# 3_USB_TO_UART.net
KiCad netlist of a schematic drawn in Altium Designer
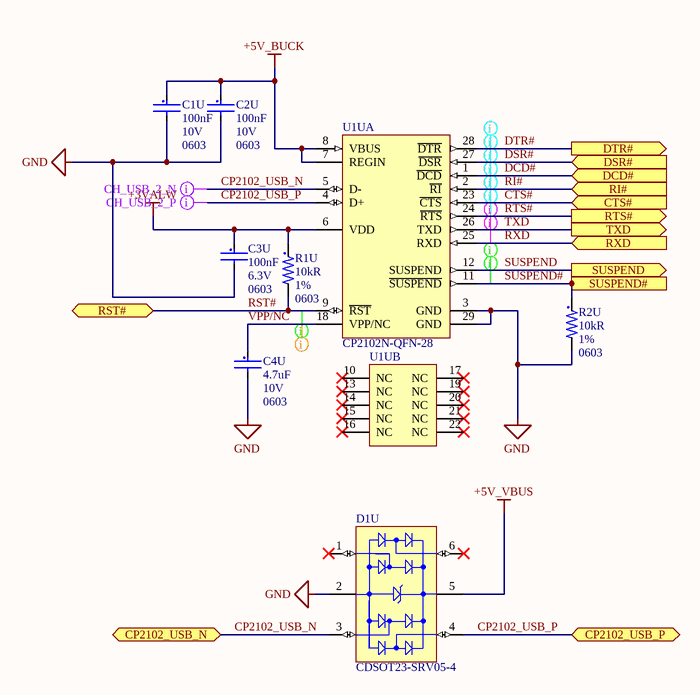
[diagram p0: 3_USB_TO_UART.SchDoc]

(export (version "E")
  (design (tool "Eeschema 10.0.6"))
  (components
    (comp (ref "C1U")
      (value "100nF")
      (footprint "C0603-IPC_C_No_Silk")
      (description "Multilayer Ceramic Capacitor, 0.1 uF, 10 V, ± 10%, X7R, 0603 [1608 Metric]")
      (fields
        (field (name "MANUFACTURER") "KEMET")
        (field (name "MANUFACTURER PART NUMBER") "C0603C104K8RACTU")
        (field (name "VOLTAGE RATING (DC)") "10V")
        (field (name "CASE/PACKAGE") "0603")
      )
      (libsource (lib "Lib_Capacitor_0603") (part "100nF_10V"))
    )
    (comp (ref "C2U")
      (value "100nF")
      (footprint "C0603-IPC_C_No_Silk")
      (description "Multilayer Ceramic Capacitor, 0.1 uF, 10 V, ± 10%, X7R, 0603 [1608 Metric]")
      (fields
        (field (name "MANUFACTURER") "KEMET")
        (field (name "MANUFACTURER PART NUMBER") "C0603C104K8RACTU")
        (field (name "VOLTAGE RATING (DC)") "10V")
        (field (name "CASE/PACKAGE") "0603")
      )
      (libsource (lib "Lib_Capacitor_0603") (part "100nF_10V"))
    )
    (comp (ref "C3U")
      (value "100nF")
      (footprint "C0603-IPC_C_No_Silk")
      (description "Cap Cer 0.1UF 6.3V X7R 0603")
      (fields
        (field (name "MANUFACTURER") "KYOCERA AVX")
        (field (name "MANUFACTURER PART NUMBER") "KGM15AR70J104KM")
        (field (name "VOLTAGE") "6.3V")
        (field (name "PACKAGE") "0603")
      )
      (libsource (lib "Lib_Capacitor_0603") (part "100nF_6.3V"))
    )
    (comp (ref "C4U")
      (value "4.7uF")
      (footprint "C0603-IPC_C_No_Silk")
      (description "Multilayer Ceramic Capacitor, 4.7 uF, 10 V, ± 10%, X5R, 0603 [1608 Metric]")
      (fields
        (field (name "MANUFACTURER") "Samsung")
        (field (name "MANUFACTURER PART NUMBER") "CL10A475KP8NNNC")
        (field (name "VOLTAGE RATING (DC)") "10V")
        (field (name "CASE/PACKAGE") "0603")
      )
      (libsource (lib "Lib_Capacitor_0603") (part "4.7uF_10V"))
    )
    (comp (ref "D1U")
      (value "CDSOT23-SRV05-4")
      (footprint "SOT23-6-IPC_C")
      (description "TVS DIODE 5V 15V SOT23-6")
      (fields
        (field (name "MANUFACTURER") "Bourns Inc.")
        (field (name "OCTOPART") "https://octopart.com/cdsot23-srv05-4-bourns-1679449")
      )
      (libsource (lib "Lib_IC_ESD") (part "SRV05-4"))
    )
    (comp (ref "R1U")
      (value "10kR")
      (footprint "R0603-MFG")
      (description "SMD Chip Resistor, 10 kOhm, ± 1%, 100 mW, 0603 [1608 Metric], Thick Film, General Purpose")
      (fields
        (field (name "MANUFACTURER") "Yageo")
        (field (name "MANUFACTURER PART NUMBER") "RC0603FR-0710KL")
        (field (name "TOLERANCE") "1%")
        (field (name "CASE/PACKAGE") "0603")
      )
      (libsource (lib "Lib_Register_0603") (part "10K"))
    )
    (comp (ref "R2U")
      (value "10kR")
      (footprint "R0603-MFG")
      (description "SMD Chip Resistor, 10 kOhm, ± 1%, 100 mW, 0603 [1608 Metric], Thick Film, General Purpose")
      (fields
        (field (name "MANUFACTURER") "Yageo")
        (field (name "MANUFACTURER PART NUMBER") "RC0603FR-0710KL")
        (field (name "TOLERANCE") "1%")
        (field (name "CASE/PACKAGE") "0603")
      )
      (libsource (lib "Lib_Register_0603") (part "10K"))
    )
    (comp (ref "U1U")
      (value "CP2102N-QFN-28")
      (footprint "QFN28_IPC_A")
      (description "Single-Chip USB to UART Bridge, 1024 Bytes EEPROM, -40 to 85 degC, 28-pin QFN, Tube")
      (fields (field (name "MANUFACTURER") "Silicon Labs") (field (name "PARTNUMBER") "CP2102-GM"))
      (libsource (lib "Lib_IC_UART") (part "CP2102N-QFN-28"))
    )
  )
  (nets
    (net (code "1") (name "+3VALW") (class "Default")
      (node (ref "C3U") (pin "1") (pinfunction "1_1") (pintype "passive"))
      (node (ref "R1U") (pin "1") (pinfunction "1_1") (pintype "passive"))
      (node (ref "U1U") (pin "6") (pinfunction "VDD_6") (pintype "power_in"))
    )
    (net (code "2") (name "+5V_BUCK") (class "Default")
      (node (ref "C1U") (pin "1") (pinfunction "1_1") (pintype "passive"))
      (node (ref "C2U") (pin "1") (pinfunction "1_1") (pintype "passive"))
      (node (ref "U1U") (pin "7") (pinfunction "REGIN_7") (pintype "power_in"))
      (node (ref "U1U") (pin "8") (pinfunction "VBUS_8") (pintype "input"))
    )
    (net (code "3") (name "+5V_VBUS") (class "Default")
      (node (ref "D1U") (pin "5") (pinfunction "VBUS_5") (pintype "power_in"))
    )
    (net (code "4") (name "/CP2102_USB_N") (class "Default")
      (node (ref "D1U") (pin "3") (pinfunction "I/O_2_3") (pintype "bidirectional"))
      (node (ref "U1U") (pin "5") (pinfunction "D-_5") (pintype "bidirectional"))
    )
    (net (code "5") (name "/CP2102_USB_P") (class "Default")
      (node (ref "D1U") (pin "4") (pinfunction "I/O_3_4") (pintype "bidirectional"))
      (node (ref "U1U") (pin "4") (pinfunction "D+_4") (pintype "bidirectional"))
    )
    (net (code "6") (name "/CTS#") (class "Default")
      (node (ref "U1U") (pin "23") (pinfunction "~{CTS}_23") (pintype "input"))
    )
    (net (code "7") (name "/DCD#") (class "Default")
      (node (ref "U1U") (pin "1") (pinfunction "~{DCD}_1") (pintype "input"))
    )
    (net (code "8") (name "/DSR#") (class "Default")
      (node (ref "U1U") (pin "27") (pinfunction "~{DSR}_27") (pintype "input"))
    )
    (net (code "9") (name "/DTR#") (class "Default")
      (node (ref "U1U") (pin "28") (pinfunction "~{DTR}_28") (pintype "output"))
    )
    (net (code "10") (name "/RI#") (class "Default")
      (node (ref "U1U") (pin "2") (pinfunction "~{RI}_2") (pintype "input"))
    )
    (net (code "11") (name "/RST#") (class "Default")
      (node (ref "R1U") (pin "2") (pinfunction "2_2") (pintype "passive"))
      (node (ref "U1U") (pin "9") (pinfunction "~{RST}_9") (pintype "bidirectional"))
    )
    (net (code "12") (name "/RTS#") (class "Default")
      (node (ref "U1U") (pin "24") (pinfunction "~{RTS}_24") (pintype "output"))
    )
    (net (code "13") (name "/RXD") (class "Default")
      (node (ref "U1U") (pin "25") (pinfunction "RXD_25") (pintype "input"))
    )
    (net (code "14") (name "/SUSPEND") (class "Default")
      (node (ref "U1U") (pin "12") (pinfunction "SUSPEND_12") (pintype "output"))
    )
    (net (code "15") (name "/SUSPEND#") (class "Default")
      (node (ref "R2U") (pin "1") (pinfunction "1_1") (pintype "passive"))
      (node (ref "U1U") (pin "11") (pinfunction "~{SUSPEND}_11") (pintype "output"))
    )
    (net (code "16") (name "/TXD") (class "Default")
      (node (ref "U1U") (pin "26") (pinfunction "TXD_26") (pintype "output"))
    )
    (net (code "17") (name "/VPP{slash}NC") (class "Default")
      (node (ref "C4U") (pin "1") (pinfunction "1_1") (pintype "passive"))
      (node (ref "U1U") (pin "18") (pinfunction "VPP/NC_18") (pintype "passive"))
    )
    (net (code "18") (name "GND") (class "Default")
      (node (ref "C1U") (pin "2") (pinfunction "2_2") (pintype "passive"))
      (node (ref "C2U") (pin "2") (pinfunction "2_2") (pintype "passive"))
      (node (ref "C3U") (pin "2") (pinfunction "2_2") (pintype "passive"))
      (node (ref "C4U") (pin "2") (pinfunction "2_2") (pintype "passive"))
      (node (ref "D1U") (pin "2") (pinfunction "GND_2") (pintype "power_in"))
      (node (ref "R2U") (pin "2") (pinfunction "2_2") (pintype "passive"))
      (node (ref "U1U") (pin "29") (pinfunction "GND_29") (pintype "power_in"))
      (node (ref "U1U") (pin "3") (pinfunction "GND_3") (pintype "power_in"))
    )
    (net (code "19") (name "unconnected-(D1U-I{slash}O_1-Pad1)") (class "Default")
      (node (ref "D1U") (pin "1") (pinfunction "I/O_1_1") (pintype "bidirectional+no_connect"))
    )
    (net (code "20") (name "unconnected-(D1U-I{slash}O_4-Pad6)") (class "Default")
      (node (ref "D1U") (pin "6") (pinfunction "I/O_4_6") (pintype "bidirectional+no_connect"))
    )
    (net (code "21") (name "unconnected-(U1UB-NC-Pad10)") (class "Default")
      (node (ref "U1U") (pin "10") (pinfunction "NC_10") (pintype "passive+no_connect"))
    )
    (net (code "22") (name "unconnected-(U1UB-NC-Pad13)") (class "Default")
      (node (ref "U1U") (pin "13") (pinfunction "NC_13") (pintype "passive+no_connect"))
    )
    (net (code "23") (name "unconnected-(U1UB-NC-Pad14)") (class "Default")
      (node (ref "U1U") (pin "14") (pinfunction "NC_14") (pintype "passive+no_connect"))
    )
    (net (code "24") (name "unconnected-(U1UB-NC-Pad15)") (class "Default")
      (node (ref "U1U") (pin "15") (pinfunction "NC_15") (pintype "passive+no_connect"))
    )
    (net (code "25") (name "unconnected-(U1UB-NC-Pad16)") (class "Default")
      (node (ref "U1U") (pin "16") (pinfunction "NC_16") (pintype "passive+no_connect"))
    )
    (net (code "26") (name "unconnected-(U1UB-NC-Pad17)") (class "Default")
      (node (ref "U1U") (pin "17") (pinfunction "NC_17") (pintype "passive+no_connect"))
    )
    (net (code "27") (name "unconnected-(U1UB-NC-Pad19)") (class "Default")
      (node (ref "U1U") (pin "19") (pinfunction "NC_19") (pintype "passive+no_connect"))
    )
    (net (code "28") (name "unconnected-(U1UB-NC-Pad20)") (class "Default")
      (node (ref "U1U") (pin "20") (pinfunction "NC_20") (pintype "passive+no_connect"))
    )
    (net (code "29") (name "unconnected-(U1UB-NC-Pad21)") (class "Default")
      (node (ref "U1U") (pin "21") (pinfunction "NC_21") (pintype "passive+no_connect"))
    )
    (net (code "30") (name "unconnected-(U1UB-NC-Pad22)") (class "Default")
      (node (ref "U1U") (pin "22") (pinfunction "NC_22") (pintype "passive+no_connect"))
    )
  )
)
